# 1x9_to_1x9.net
KiCad netlist of a schematic drawn in EAGLE
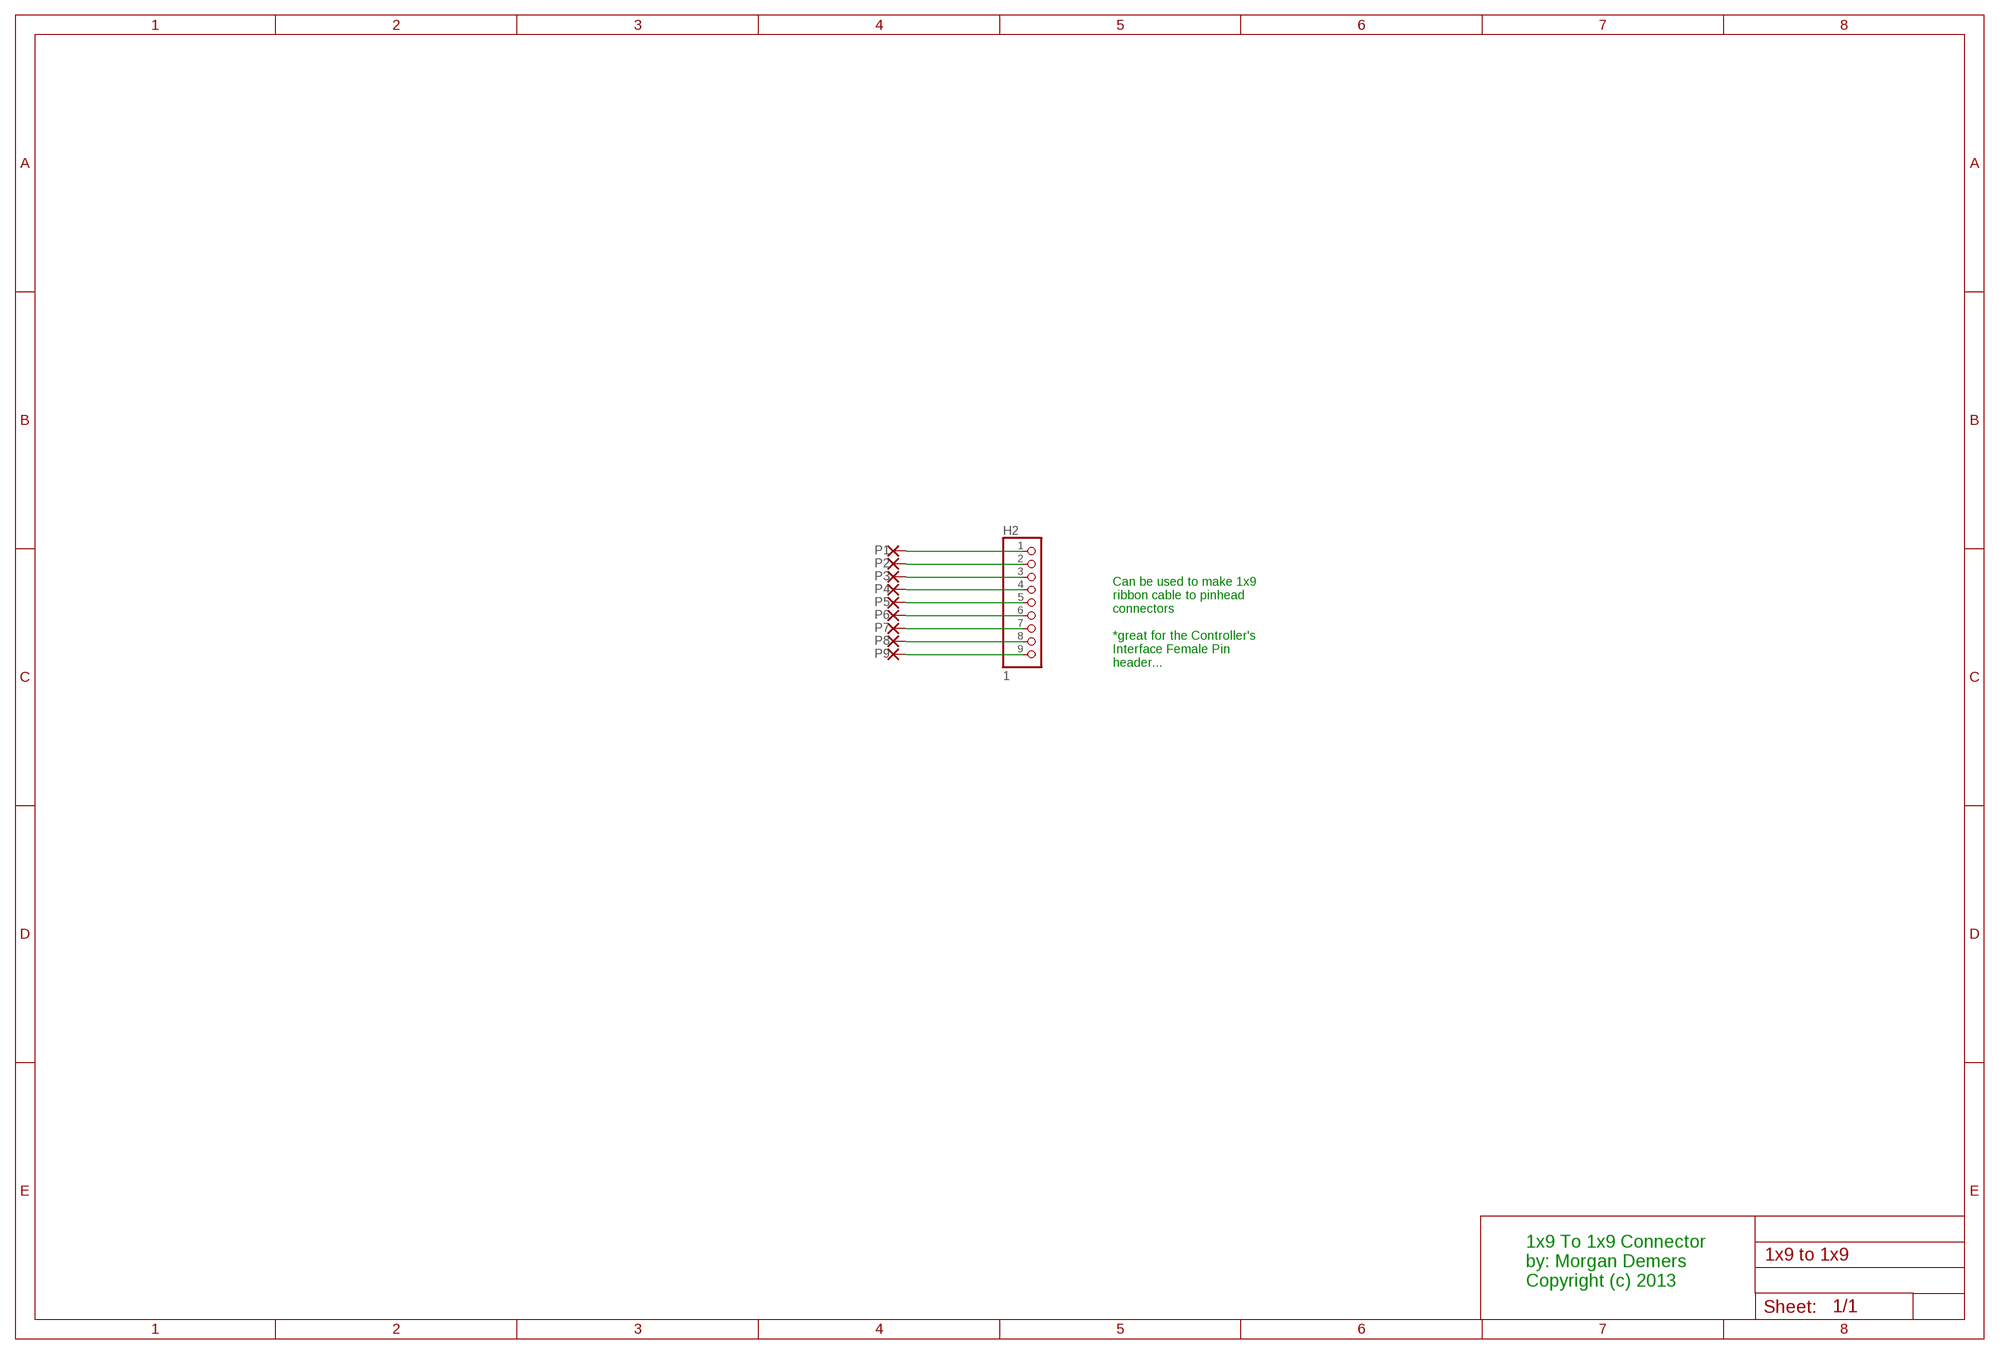
[diagram p0: schematic, sheet 1]

(export (version "E")
  (design (tool "Eeschema 10.0.6"))
  (components
    (comp (ref "H2")
      (value "1")
      (footprint "eagle-import:1X09")
      (libsource (lib "eagle-import") (part "PINHD-1X9"))
    )
    (comp (ref "P1")
      (value "1,6/0,9")
      (footprint "eagle-import:1,6_0,9")
      (libsource (lib "eagle-import") (part "1,6/0,9"))
    )
    (comp (ref "P2")
      (value "1,6/0,9")
      (footprint "eagle-import:1,6_0,9")
      (libsource (lib "eagle-import") (part "1,6/0,9"))
    )
    (comp (ref "P3")
      (value "1,6/0,9")
      (footprint "eagle-import:1,6_0,9")
      (libsource (lib "eagle-import") (part "1,6/0,9"))
    )
    (comp (ref "P4")
      (value "1,6/0,9")
      (footprint "eagle-import:1,6_0,9")
      (libsource (lib "eagle-import") (part "1,6/0,9"))
    )
    (comp (ref "P5")
      (value "1,6/0,9")
      (footprint "eagle-import:1,6_0,9")
      (libsource (lib "eagle-import") (part "1,6/0,9"))
    )
    (comp (ref "P6")
      (value "1,6/0,9")
      (footprint "eagle-import:1,6_0,9")
      (libsource (lib "eagle-import") (part "1,6/0,9"))
    )
    (comp (ref "P7")
      (value "1,6/0,9")
      (footprint "eagle-import:1,6_0,9")
      (libsource (lib "eagle-import") (part "1,6/0,9"))
    )
    (comp (ref "P8")
      (value "1,6/0,9")
      (footprint "eagle-import:1,6_0,9")
      (libsource (lib "eagle-import") (part "1,6/0,9"))
    )
    (comp (ref "P9")
      (value "1,6/0,9")
      (footprint "eagle-import:1,6_0,9")
      (libsource (lib "eagle-import") (part "1,6/0,9"))
    )
  )
  (nets
    (net (code "1") (name "Net-(P1-P)") (class "Default")
      (node (ref "H2") (pin "1") (pinfunction "1_1") (pintype "passive"))
      (node (ref "P1") (pin "1") (pinfunction "P_1") (pintype "passive"))
    )
    (net (code "2") (name "Net-(P2-P)") (class "Default")
      (node (ref "H2") (pin "2") (pinfunction "2_2") (pintype "passive"))
      (node (ref "P2") (pin "1") (pinfunction "P_1") (pintype "passive"))
    )
    (net (code "3") (name "Net-(P3-P)") (class "Default")
      (node (ref "H2") (pin "3") (pinfunction "3_3") (pintype "passive"))
      (node (ref "P3") (pin "1") (pinfunction "P_1") (pintype "passive"))
    )
    (net (code "4") (name "Net-(P4-P)") (class "Default")
      (node (ref "H2") (pin "4") (pinfunction "4_4") (pintype "passive"))
      (node (ref "P4") (pin "1") (pinfunction "P_1") (pintype "passive"))
    )
    (net (code "5") (name "Net-(P5-P)") (class "Default")
      (node (ref "H2") (pin "5") (pinfunction "5_5") (pintype "passive"))
      (node (ref "P5") (pin "1") (pinfunction "P_1") (pintype "passive"))
    )
    (net (code "6") (name "Net-(P6-P)") (class "Default")
      (node (ref "H2") (pin "6") (pinfunction "6_6") (pintype "passive"))
      (node (ref "P6") (pin "1") (pinfunction "P_1") (pintype "passive"))
    )
    (net (code "7") (name "Net-(P7-P)") (class "Default")
      (node (ref "H2") (pin "7") (pinfunction "7_7") (pintype "passive"))
      (node (ref "P7") (pin "1") (pinfunction "P_1") (pintype "passive"))
    )
    (net (code "8") (name "Net-(P8-P)") (class "Default")
      (node (ref "H2") (pin "8") (pinfunction "8_8") (pintype "passive"))
      (node (ref "P8") (pin "1") (pinfunction "P_1") (pintype "passive"))
    )
    (net (code "9") (name "Net-(P9-P)") (class "Default")
      (node (ref "H2") (pin "9") (pinfunction "9_9") (pintype "passive"))
      (node (ref "P9") (pin "1") (pinfunction "P_1") (pintype "passive"))
    )
  )
)
